# MicroLRS.net
KiCad netlist of a schematic drawn in EAGLE
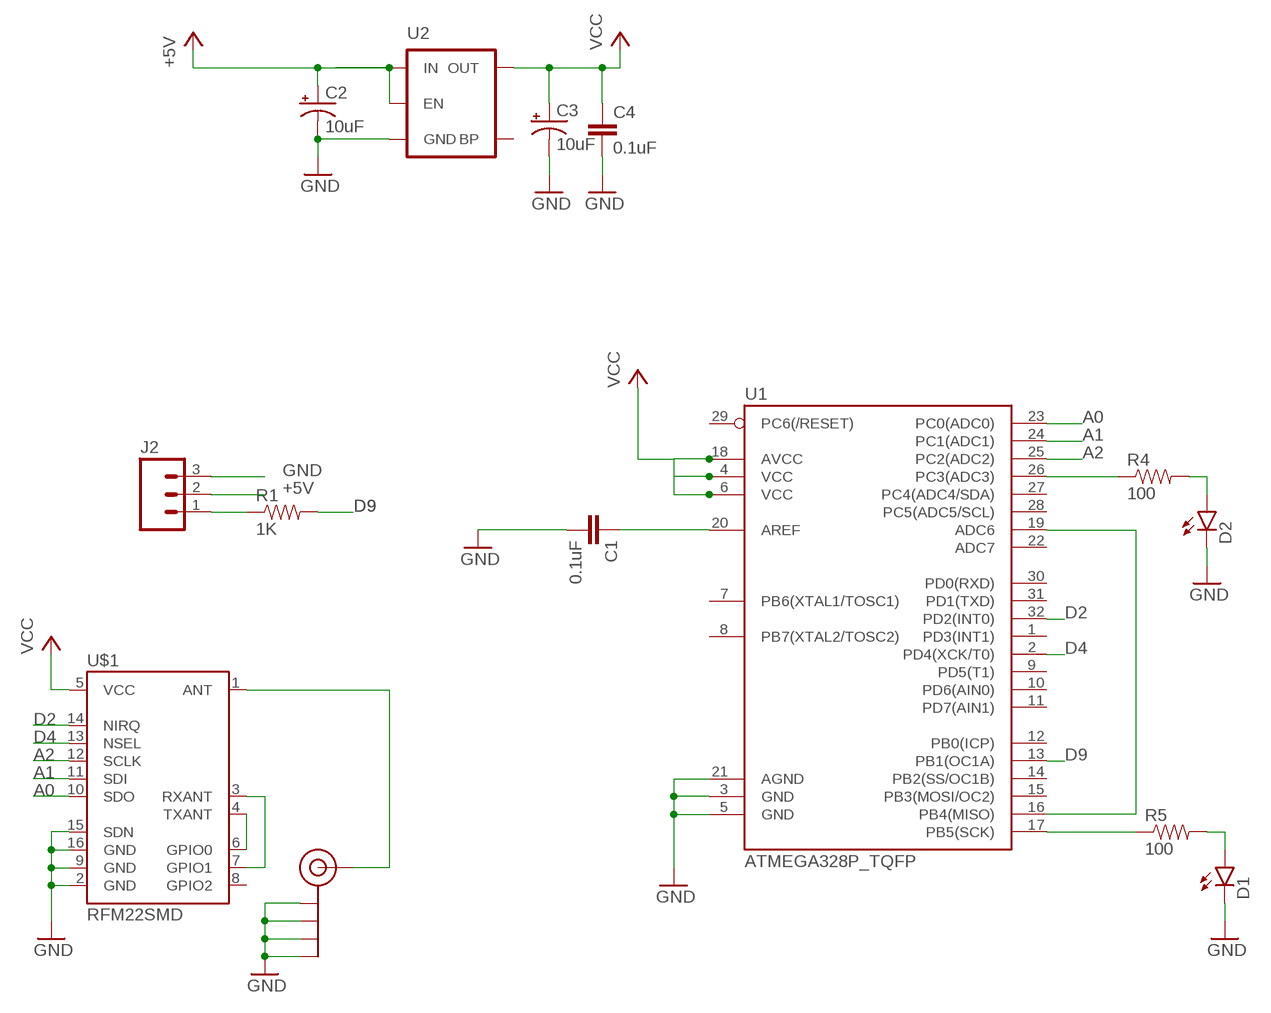
[diagram p0: schematic, sheet 1]

(export (version "E")
  (design (tool "Eeschema 10.0.6"))
  (components
    (comp (ref "C1")
      (value "0.1uF")
      (footprint "eagle-import:0402-CAP")
      (libsource (lib "eagle-import") (part "0.1UF-16V(+-10%)(0402)"))
    )
    (comp (ref "C2")
      (value "10uF")
      (footprint "eagle-import:0603-POL")
      (libsource (lib "eagle-import") (part "10UF-6.3V-20%(0603)(TANT){dblquote}"))
    )
    (comp (ref "C3")
      (value "10uF")
      (footprint "eagle-import:0603-POL")
      (libsource (lib "eagle-import") (part "10UF-6.3V-20%(0603)(TANT){dblquote}"))
    )
    (comp (ref "C4")
      (value "0.1uF")
      (footprint "eagle-import:0603-CAP")
      (libsource (lib "eagle-import") (part "0.1UF-25V-5%(0603)"))
    )
    (comp (ref "D1")
      (value "LED0603")
      (footprint "eagle-import:LED-0603")
      (libsource (lib "eagle-import") (part "LED0603"))
    )
    (comp (ref "D2")
      (value "LED0603")
      (footprint "eagle-import:LED-0603")
      (libsource (lib "eagle-import") (part "LED0603"))
    )
    (comp (ref "J$1")
      (value "SMA_EDGE")
      (footprint "eagle-import:SMA-EDGE")
      (libsource (lib "eagle-import") (part "SMA_EDGE"))
    )
    (comp (ref "J2")
      (value "M03PTH")
      (footprint "eagle-import:1X03")
      (libsource (lib "eagle-import") (part "M03PTH"))
    )
    (comp (ref "R1")
      (value "1K")
      (footprint "eagle-import:0603-RES")
      (libsource (lib "eagle-import") (part "1KOHM-1/10W-1%(0603)"))
    )
    (comp (ref "R4")
      (value "100")
      (footprint "eagle-import:0603-RES")
      (libsource (lib "eagle-import") (part "100OHM-1/10W-1%(0603)"))
    )
    (comp (ref "R5")
      (value "100")
      (footprint "eagle-import:0603-RES")
      (libsource (lib "eagle-import") (part "100OHM-1/10W-1%(0603)"))
    )
    (comp (ref "U$1")
      (value "RFM22SMD")
      (footprint "eagle-import:RFM22-XXX-S2")
      (libsource (lib "eagle-import") (part "RFM22SMD"))
    )
    (comp (ref "U1")
      (value "ATMEGA328P_TQFP")
      (footprint "eagle-import:TQFP32-08")
      (libsource (lib "eagle-import") (part "ATMEGA328P_TQFP"))
    )
    (comp (ref "U2")
      (value "MIC52053.3V")
      (footprint "eagle-import:SOT23-5")
      (libsource (lib "eagle-import") (part "MIC52053.3V"))
    )
  )
  (nets
    (net (code "1") (name "+5V") (class "Default")
      (node (ref "C2") (pin "A") (pinfunction "+_A") (pintype "passive"))
      (node (ref "J2") (pin "2") (pinfunction "2_2") (pintype "passive"))
      (node (ref "U2") (pin "1") (pinfunction "IN_1") (pintype "input"))
      (node (ref "U2") (pin "3") (pinfunction "EN_3") (pintype "input"))
    )
    (net (code "2") (name "/A0") (class "Default")
      (node (ref "U$1") (pin "10") (pinfunction "SDO_10") (pintype "output"))
      (node (ref "U1") (pin "23") (pinfunction "PC0(ADC0)_23") (pintype "bidirectional"))
    )
    (net (code "3") (name "/A1") (class "Default")
      (node (ref "U$1") (pin "11") (pinfunction "SDI_11") (pintype "input"))
      (node (ref "U1") (pin "24") (pinfunction "PC1(ADC1)_24") (pintype "bidirectional"))
    )
    (net (code "4") (name "/A2") (class "Default")
      (node (ref "U$1") (pin "12") (pinfunction "SCLK_12") (pintype "input"))
      (node (ref "U1") (pin "25") (pinfunction "PC2(ADC2)_25") (pintype "bidirectional"))
    )
    (net (code "5") (name "/D2") (class "Default")
      (node (ref "U$1") (pin "14") (pinfunction "NIRQ_14") (pintype "output"))
      (node (ref "U1") (pin "32") (pinfunction "PD2(INT0)_32") (pintype "bidirectional"))
    )
    (net (code "6") (name "/D4") (class "Default")
      (node (ref "U$1") (pin "13") (pinfunction "NSEL_13") (pintype "input"))
      (node (ref "U1") (pin "2") (pinfunction "PD4(XCK/T0)_2") (pintype "bidirectional"))
    )
    (net (code "7") (name "/D9") (class "Default")
      (node (ref "R1") (pin "2") (pinfunction "2_2") (pintype "passive"))
      (node (ref "U1") (pin "13") (pinfunction "PB1(OC1A)_13") (pintype "bidirectional"))
    )
    (net (code "8") (name "GND") (class "Default")
      (node (ref "C1") (pin "2") (pinfunction "2_2") (pintype "passive"))
      (node (ref "C2") (pin "K") (pinfunction "-_K") (pintype "passive"))
      (node (ref "C3") (pin "K") (pinfunction "-_K") (pintype "passive"))
      (node (ref "C4") (pin "2") (pinfunction "2_2") (pintype "passive"))
      (node (ref "D1") (pin "C") (pinfunction "C_C") (pintype "passive"))
      (node (ref "D2") (pin "C") (pinfunction "C_C") (pintype "passive"))
      (node (ref "J$1") (pin "GND@0") (pinfunction "GND_GND@0") (pintype "bidirectional"))
      (node (ref "J$1") (pin "GND@1") (pinfunction "GND_GND@1") (pintype "bidirectional"))
      (node (ref "J$1") (pin "GND@2") (pinfunction "GND_GND@2") (pintype "bidirectional"))
      (node (ref "J$1") (pin "GND@3") (pinfunction "GND_GND@3") (pintype "bidirectional"))
      (node (ref "J2") (pin "3") (pinfunction "3_3") (pintype "passive"))
      (node (ref "U$1") (pin "15") (pinfunction "SDN_15") (pintype "input"))
      (node (ref "U$1") (pin "16") (pinfunction "GND_16") (pintype "power_in"))
      (node (ref "U$1") (pin "2") (pinfunction "GND_2") (pintype "power_in"))
      (node (ref "U$1") (pin "9") (pinfunction "GND_9") (pintype "power_in"))
      (node (ref "U1") (pin "21") (pinfunction "AGND_21") (pintype "bidirectional"))
      (node (ref "U1") (pin "3") (pinfunction "GND_3") (pintype "bidirectional"))
      (node (ref "U1") (pin "5") (pinfunction "GND_5") (pintype "bidirectional"))
      (node (ref "U2") (pin "2") (pinfunction "GND_2") (pintype "input"))
    )
    (net (code "9") (name "Net-(D1-PadA)") (class "Default")
      (node (ref "D1") (pin "A") (pinfunction "A_A") (pintype "passive"))
      (node (ref "R5") (pin "2") (pinfunction "2_2") (pintype "passive"))
    )
    (net (code "10") (name "Net-(D2-PadA)") (class "Default")
      (node (ref "D2") (pin "A") (pinfunction "A_A") (pintype "passive"))
      (node (ref "R4") (pin "2") (pinfunction "2_2") (pintype "passive"))
    )
    (net (code "11") (name "Net-(J$1-SIGNAL)") (class "Default")
      (node (ref "J$1") (pin "SIG") (pinfunction "SIGNAL_SIG") (pintype "bidirectional"))
      (node (ref "U$1") (pin "1") (pinfunction "ANT_1") (pintype "bidirectional"))
    )
    (net (code "12") (name "Net-(J2-Pad1)") (class "Default")
      (node (ref "J2") (pin "1") (pinfunction "1_1") (pintype "passive"))
      (node (ref "R1") (pin "1") (pinfunction "1_1") (pintype "passive"))
    )
    (net (code "13") (name "Net-(U$1-GPIO0)") (class "Default")
      (node (ref "U$1") (pin "4") (pinfunction "TXANT_4") (pintype "input"))
      (node (ref "U$1") (pin "6") (pinfunction "GPIO0_6") (pintype "bidirectional"))
    )
    (net (code "14") (name "Net-(U$1-GPIO1)") (class "Default")
      (node (ref "U$1") (pin "3") (pinfunction "RXANT_3") (pintype "input"))
      (node (ref "U$1") (pin "7") (pinfunction "GPIO1_7") (pintype "bidirectional"))
    )
    (net (code "15") (name "Net-(U1-ADC6)") (class "Default")
      (node (ref "U1") (pin "16") (pinfunction "PB4(MISO)_16") (pintype "bidirectional"))
      (node (ref "U1") (pin "19") (pinfunction "ADC6_19") (pintype "bidirectional"))
    )
    (net (code "16") (name "Net-(U1-AREF)") (class "Default")
      (node (ref "C1") (pin "1") (pinfunction "1_1") (pintype "passive"))
      (node (ref "U1") (pin "20") (pinfunction "AREF_20") (pintype "bidirectional"))
    )
    (net (code "17") (name "Net-(U1-PB5(SCK))") (class "Default")
      (node (ref "R5") (pin "1") (pinfunction "1_1") (pintype "passive"))
      (node (ref "U1") (pin "17") (pinfunction "PB5(SCK)_17") (pintype "bidirectional"))
    )
    (net (code "18") (name "Net-(U1-PC3(ADC3))") (class "Default")
      (node (ref "R4") (pin "1") (pinfunction "1_1") (pintype "passive"))
      (node (ref "U1") (pin "26") (pinfunction "PC3(ADC3)_26") (pintype "bidirectional"))
    )
    (net (code "19") (name "VCC") (class "Default")
      (node (ref "C3") (pin "A") (pinfunction "+_A") (pintype "passive"))
      (node (ref "C4") (pin "1") (pinfunction "1_1") (pintype "passive"))
      (node (ref "U$1") (pin "5") (pinfunction "VCC_5") (pintype "bidirectional"))
      (node (ref "U1") (pin "18") (pinfunction "AVCC_18") (pintype "bidirectional"))
      (node (ref "U1") (pin "4") (pinfunction "VCC_4") (pintype "bidirectional"))
      (node (ref "U1") (pin "6") (pinfunction "VCC_6") (pintype "bidirectional"))
      (node (ref "U2") (pin "5") (pinfunction "OUT_5") (pintype "passive"))
    )
    (net (code "20") (name "unconnected-(U$1-GPIO2-Pad8)") (class "Default")
      (node (ref "U$1") (pin "8") (pinfunction "GPIO2_8") (pintype "bidirectional"))
    )
    (net (code "21") (name "unconnected-(U1-ADC7-Pad22)") (class "Default")
      (node (ref "U1") (pin "22") (pinfunction "ADC7_22") (pintype "bidirectional"))
    )
    (net (code "22") (name "unconnected-(U1-PB0(ICP)-Pad12)") (class "Default")
      (node (ref "U1") (pin "12") (pinfunction "PB0(ICP)_12") (pintype "bidirectional"))
    )
    (net (code "23") (name "unconnected-(U1-PB2(SS{slash}OC1B)-Pad14)") (class "Default")
      (node (ref "U1") (pin "14") (pinfunction "PB2(SS/OC1B)_14") (pintype "bidirectional"))
    )
    (net (code "24") (name "unconnected-(U1-PB3(MOSI{slash}OC2)-Pad15)") (class "Default")
      (node (ref "U1") (pin "15") (pinfunction "PB3(MOSI/OC2)_15") (pintype "bidirectional"))
    )
    (net (code "25") (name "unconnected-(U1-PB6(XTAL1{slash}TOSC1)-Pad7)") (class "Default")
      (node (ref "U1") (pin "7") (pinfunction "PB6(XTAL1/TOSC1)_7") (pintype "bidirectional"))
    )
    (net (code "26") (name "unconnected-(U1-PB7(XTAL2{slash}TOSC2)-Pad8)") (class "Default")
      (node (ref "U1") (pin "8") (pinfunction "PB7(XTAL2/TOSC2)_8") (pintype "bidirectional"))
    )
    (net (code "27") (name "unconnected-(U1-PC4(ADC4{slash}SDA)-Pad27)") (class "Default")
      (node (ref "U1") (pin "27") (pinfunction "PC4(ADC4/SDA)_27") (pintype "bidirectional"))
    )
    (net (code "28") (name "unconnected-(U1-PC5(ADC5{slash}SCL)-Pad28)") (class "Default")
      (node (ref "U1") (pin "28") (pinfunction "PC5(ADC5/SCL)_28") (pintype "bidirectional"))
    )
    (net (code "29") (name "unconnected-(U1-PC6({slash}RESET)-Pad29)") (class "Default")
      (node (ref "U1") (pin "29") (pinfunction "PC6(/RESET)_29") (pintype "bidirectional"))
    )
    (net (code "30") (name "unconnected-(U1-PD0(RXD)-Pad30)") (class "Default")
      (node (ref "U1") (pin "30") (pinfunction "PD0(RXD)_30") (pintype "bidirectional"))
    )
    (net (code "31") (name "unconnected-(U1-PD1(TXD)-Pad31)") (class "Default")
      (node (ref "U1") (pin "31") (pinfunction "PD1(TXD)_31") (pintype "bidirectional"))
    )
    (net (code "32") (name "unconnected-(U1-PD3(INT1)-Pad1)") (class "Default")
      (node (ref "U1") (pin "1") (pinfunction "PD3(INT1)_1") (pintype "bidirectional"))
    )
    (net (code "33") (name "unconnected-(U1-PD5(T1)-Pad9)") (class "Default")
      (node (ref "U1") (pin "9") (pinfunction "PD5(T1)_9") (pintype "bidirectional"))
    )
    (net (code "34") (name "unconnected-(U1-PD6(AIN0)-Pad10)") (class "Default")
      (node (ref "U1") (pin "10") (pinfunction "PD6(AIN0)_10") (pintype "bidirectional"))
    )
    (net (code "35") (name "unconnected-(U1-PD7(AIN1)-Pad11)") (class "Default")
      (node (ref "U1") (pin "11") (pinfunction "PD7(AIN1)_11") (pintype "bidirectional"))
    )
    (net (code "36") (name "unconnected-(U2-BP-Pad4)") (class "Default")
      (node (ref "U2") (pin "4") (pinfunction "BP_4") (pintype "input"))
    )
  )
)
